# bbtc-logic.net
KiCad netlist of a schematic drawn in EAGLE
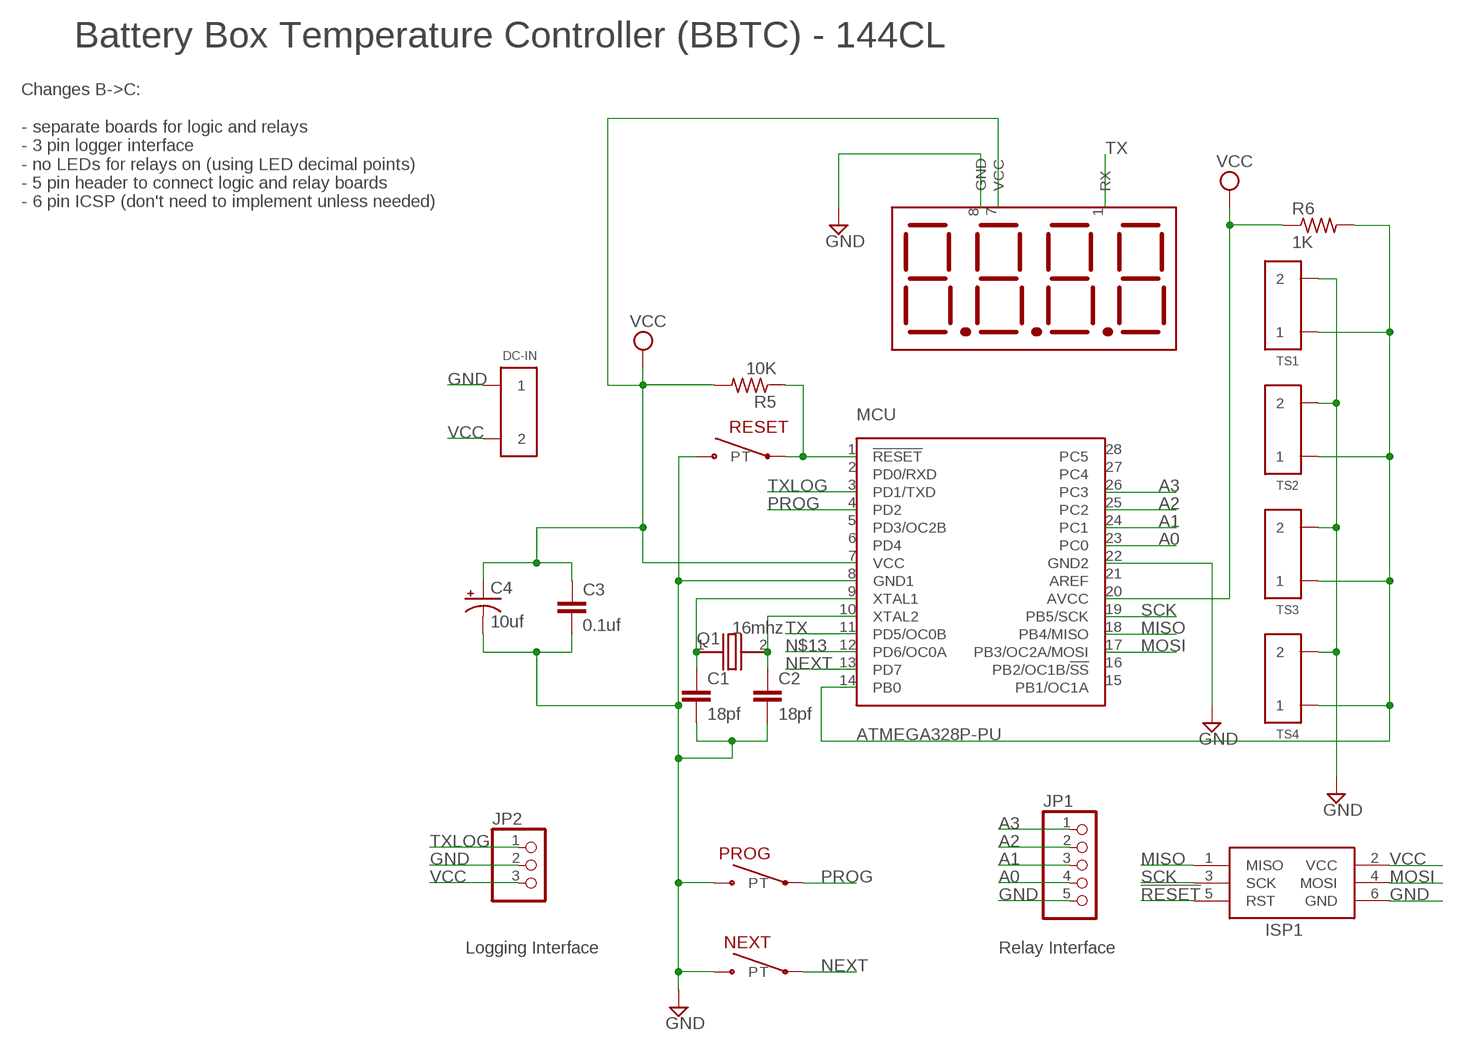
[diagram p0: schematic, sheet 1]

(export (version "E")
  (design (tool "Eeschema 10.0.6"))
  (components
    (comp (ref "4-DIG-DISPLAY")
      (value "4-DIGIT-DISPLAY")
      (footprint "eagle-import:3SIL-OF-8")
      (libsource (lib "eagle-import") (part "4-DIGIT-DISPLAY"))
    )
    (comp (ref "C1")
      (value "18pf")
      (footprint "eagle-import:C0805")
      (libsource (lib "eagle-import") (part "C-EUC0805"))
    )
    (comp (ref "C2")
      (value "18pf")
      (footprint "eagle-import:C0805")
      (libsource (lib "eagle-import") (part "C-EUC0805"))
    )
    (comp (ref "C3")
      (value "0.1uf")
      (footprint "eagle-import:C0805")
      (libsource (lib "eagle-import") (part "C-EUC0805"))
    )
    (comp (ref "C4")
      (value "10uf")
      (footprint "eagle-import:E2-4")
      (libsource (lib "eagle-import") (part "CPOL-USE2-4"))
    )
    (comp (ref "DC-IN")
      (value "SCREW-CLAMP-1255")
      (footprint "eagle-import:SCREW-CLAMP-ADAFRUIT-2X3.5MM")
      (libsource (lib "eagle-import") (part "SCREW-CLAMP-1255"))
    )
    (comp (ref "ISP1")
      (value "AVRISP-6")
      (footprint "eagle-import:AVRISP")
      (libsource (lib "eagle-import") (part "AVRISP-6"))
    )
    (comp (ref "JP1")
      (value "PINHD-1X5")
      (footprint "eagle-import:1X05")
      (libsource (lib "eagle-import") (part "PINHD-1X5"))
    )
    (comp (ref "JP2")
      (value "PINHD-1X3")
      (footprint "eagle-import:1X03")
      (libsource (lib "eagle-import") (part "PINHD-1X3"))
    )
    (comp (ref "MCU")
      (value "ATMEGA328P-PU")
      (footprint "eagle-import:DIL28-3")
      (libsource (lib "eagle-import") (part "ATMEGA328P-PU"))
    )
    (comp (ref "NEXT")
      (value "SWITCH-SPST-NEW")
      (footprint "eagle-import:SWITCH-ADAFRUIT-6MM-SLIM")
      (libsource (lib "eagle-import") (part "SWITCH-SPST-NEW"))
    )
    (comp (ref "PROG")
      (value "SWITCH-SPST-NEW")
      (footprint "eagle-import:SWITCH-ADAFRUIT-6MM-SLIM")
      (libsource (lib "eagle-import") (part "SWITCH-SPST-NEW"))
    )
    (comp (ref "Q1")
      (value "16mhz")
      (footprint "eagle-import:CRYSTAL-5X3.2MM-1024")
      (libsource (lib "eagle-import") (part "CRYSTAL-5X3.2MM1024"))
    )
    (comp (ref "R5")
      (value "10K")
      (footprint "eagle-import:R0805")
      (libsource (lib "eagle-import") (part "R-US_R0805"))
    )
    (comp (ref "R6")
      (value "1K")
      (footprint "eagle-import:M0805")
      (libsource (lib "eagle-import") (part "resistor_R-US_M0805"))
    )
    (comp (ref "RESET")
      (value "SWITCH-SPST-NEW")
      (footprint "eagle-import:SWITCH-ADAFRUIT-6MM-SLIM")
      (libsource (lib "eagle-import") (part "SWITCH-SPST-NEW"))
    )
    (comp (ref "TS1")
      (value "SCREW-CLAMP-1255")
      (footprint "eagle-import:SCREW-CLAMP-ADAFRUIT-2X3.5MM")
      (libsource (lib "eagle-import") (part "SCREW-CLAMP-1255"))
    )
    (comp (ref "TS2")
      (value "SCREW-CLAMP-1255")
      (footprint "eagle-import:SCREW-CLAMP-ADAFRUIT-2X3.5MM")
      (libsource (lib "eagle-import") (part "SCREW-CLAMP-1255"))
    )
    (comp (ref "TS3")
      (value "SCREW-CLAMP-1255")
      (footprint "eagle-import:SCREW-CLAMP-ADAFRUIT-2X3.5MM")
      (libsource (lib "eagle-import") (part "SCREW-CLAMP-1255"))
    )
    (comp (ref "TS4")
      (value "SCREW-CLAMP-1255")
      (footprint "eagle-import:SCREW-CLAMP-ADAFRUIT-2X3.5MM")
      (libsource (lib "eagle-import") (part "SCREW-CLAMP-1255"))
    )
  )
  (nets
    (net (code "1") (name "/A0") (class "Default")
      (node (ref "JP1") (pin "4") (pinfunction "4_4") (pintype "passive"))
      (node (ref "MCU") (pin "23") (pinfunction "PC0_23") (pintype "bidirectional"))
    )
    (net (code "2") (name "/A1") (class "Default")
      (node (ref "JP1") (pin "3") (pinfunction "3_3") (pintype "passive"))
      (node (ref "MCU") (pin "24") (pinfunction "PC1_24") (pintype "bidirectional"))
    )
    (net (code "3") (name "/A2") (class "Default")
      (node (ref "JP1") (pin "2") (pinfunction "2_2") (pintype "passive"))
      (node (ref "MCU") (pin "25") (pinfunction "PC2_25") (pintype "bidirectional"))
    )
    (net (code "4") (name "/A3") (class "Default")
      (node (ref "JP1") (pin "1") (pinfunction "1_1") (pintype "passive"))
      (node (ref "MCU") (pin "26") (pinfunction "PC3_26") (pintype "bidirectional"))
    )
    (net (code "5") (name "/MISO") (class "Default")
      (node (ref "ISP1") (pin "1") (pinfunction "MISO_1") (pintype "input"))
      (node (ref "MCU") (pin "18") (pinfunction "PB4/MISO_18") (pintype "bidirectional"))
    )
    (net (code "6") (name "/MOSI") (class "Default")
      (node (ref "ISP1") (pin "4") (pinfunction "MOSI_4") (pintype "output"))
      (node (ref "MCU") (pin "17") (pinfunction "PB3/OC2A/MOSI_17") (pintype "bidirectional"))
    )
    (net (code "7") (name "/N$13") (class "Default")
      (node (ref "MCU") (pin "12") (pinfunction "PD6/OC0A_12") (pintype "bidirectional"))
    )
    (net (code "8") (name "/NEXT") (class "Default")
      (node (ref "MCU") (pin "13") (pinfunction "PD7_13") (pintype "bidirectional"))
      (node (ref "NEXT") (pin "T") (pinfunction "T_T") (pintype "bidirectional"))
    )
    (net (code "9") (name "/PROG") (class "Default")
      (node (ref "MCU") (pin "4") (pinfunction "PD2_4") (pintype "bidirectional"))
      (node (ref "PROG") (pin "T") (pinfunction "T_T") (pintype "bidirectional"))
    )
    (net (code "10") (name "/SCK") (class "Default")
      (node (ref "ISP1") (pin "3") (pinfunction "SCK_3") (pintype "output"))
      (node (ref "MCU") (pin "19") (pinfunction "PB5/SCK_19") (pintype "bidirectional"))
    )
    (net (code "11") (name "/TX") (class "Default")
      (node (ref "4-DIG-DISPLAY") (pin "1") (pinfunction "RX_1") (pintype "bidirectional"))
      (node (ref "MCU") (pin "11") (pinfunction "PD5/OC0B_11") (pintype "bidirectional"))
    )
    (net (code "12") (name "/TXLOG") (class "Default")
      (node (ref "JP2") (pin "1") (pinfunction "1_1") (pintype "passive"))
      (node (ref "MCU") (pin "3") (pinfunction "PD1/TXD_3") (pintype "bidirectional"))
    )
    (net (code "13") (name "/~{RESET}") (class "Default")
      (node (ref "ISP1") (pin "5") (pinfunction "RST_5") (pintype "output"))
      (node (ref "MCU") (pin "1") (pinfunction "~{RESET}_1") (pintype "bidirectional"))
      (node (ref "R5") (pin "1") (pinfunction "1_1") (pintype "passive"))
      (node (ref "RESET") (pin "T") (pinfunction "T_T") (pintype "bidirectional"))
    )
    (net (code "14") (name "GND") (class "Default")
      (node (ref "4-DIG-DISPLAY") (pin "8") (pinfunction "GND_8") (pintype "bidirectional"))
      (node (ref "C1") (pin "2") (pinfunction "2_2") (pintype "passive"))
      (node (ref "C2") (pin "2") (pinfunction "2_2") (pintype "passive"))
      (node (ref "C3") (pin "2") (pinfunction "2_2") (pintype "passive"))
      (node (ref "C4") (pin "-") (pinfunction "-_-") (pintype "passive"))
      (node (ref "DC-IN") (pin "1") (pinfunction "1_1") (pintype "bidirectional"))
      (node (ref "ISP1") (pin "6") (pinfunction "GND_6") (pintype "power_in"))
      (node (ref "JP1") (pin "5") (pinfunction "5_5") (pintype "passive"))
      (node (ref "JP2") (pin "2") (pinfunction "2_2") (pintype "passive"))
      (node (ref "MCU") (pin "22") (pinfunction "GND2_22") (pintype "bidirectional"))
      (node (ref "MCU") (pin "8") (pinfunction "GND1_8") (pintype "bidirectional"))
      (node (ref "NEXT") (pin "P") (pinfunction "P_P") (pintype "bidirectional"))
      (node (ref "PROG") (pin "P") (pinfunction "P_P") (pintype "bidirectional"))
      (node (ref "RESET") (pin "P") (pinfunction "P_P") (pintype "bidirectional"))
      (node (ref "TS1") (pin "2") (pinfunction "2_2") (pintype "bidirectional"))
      (node (ref "TS2") (pin "2") (pinfunction "2_2") (pintype "bidirectional"))
      (node (ref "TS3") (pin "2") (pinfunction "2_2") (pintype "bidirectional"))
      (node (ref "TS4") (pin "2") (pinfunction "2_2") (pintype "bidirectional"))
    )
    (net (code "15") (name "Net-(MCU-PB0)") (class "Default")
      (node (ref "MCU") (pin "14") (pinfunction "PB0_14") (pintype "bidirectional"))
      (node (ref "R6") (pin "2") (pinfunction "2_2") (pintype "passive"))
      (node (ref "TS1") (pin "1") (pinfunction "1_1") (pintype "bidirectional"))
      (node (ref "TS2") (pin "1") (pinfunction "1_1") (pintype "bidirectional"))
      (node (ref "TS3") (pin "1") (pinfunction "1_1") (pintype "bidirectional"))
      (node (ref "TS4") (pin "1") (pinfunction "1_1") (pintype "bidirectional"))
    )
    (net (code "16") (name "Net-(MCU-XTAL1)") (class "Default")
      (node (ref "C1") (pin "1") (pinfunction "1_1") (pintype "passive"))
      (node (ref "MCU") (pin "9") (pinfunction "XTAL1_9") (pintype "bidirectional"))
      (node (ref "Q1") (pin "1") (pinfunction "1_1") (pintype "bidirectional"))
    )
    (net (code "17") (name "Net-(MCU-XTAL2)") (class "Default")
      (node (ref "C2") (pin "1") (pinfunction "1_1") (pintype "passive"))
      (node (ref "MCU") (pin "10") (pinfunction "XTAL2_10") (pintype "bidirectional"))
      (node (ref "Q1") (pin "2") (pinfunction "2_2") (pintype "bidirectional"))
    )
    (net (code "18") (name "VCC") (class "Default")
      (node (ref "4-DIG-DISPLAY") (pin "7") (pinfunction "VCC_7") (pintype "bidirectional"))
      (node (ref "C3") (pin "1") (pinfunction "1_1") (pintype "passive"))
      (node (ref "C4") (pin "+") (pinfunction "+_+") (pintype "passive"))
      (node (ref "DC-IN") (pin "2") (pinfunction "2_2") (pintype "bidirectional"))
      (node (ref "ISP1") (pin "2") (pinfunction "VCC_2") (pintype "power_in"))
      (node (ref "JP2") (pin "3") (pinfunction "3_3") (pintype "passive"))
      (node (ref "MCU") (pin "20") (pinfunction "AVCC_20") (pintype "bidirectional"))
      (node (ref "MCU") (pin "7") (pinfunction "VCC_7") (pintype "bidirectional"))
      (node (ref "R5") (pin "2") (pinfunction "2_2") (pintype "passive"))
      (node (ref "R6") (pin "1") (pinfunction "1_1") (pintype "passive"))
    )
    (net (code "19") (name "unconnected-(MCU-AREF-Pad21)") (class "Default")
      (node (ref "MCU") (pin "21") (pinfunction "AREF_21") (pintype "bidirectional"))
    )
    (net (code "20") (name "unconnected-(MCU-PB1{slash}OC1A-Pad15)") (class "Default")
      (node (ref "MCU") (pin "15") (pinfunction "PB1/OC1A_15") (pintype "bidirectional"))
    )
    (net (code "21") (name "unconnected-(MCU-PB2{slash}OC1B{slash}~{SS}-Pad16)") (class "Default")
      (node (ref "MCU") (pin "16") (pinfunction "PB2/OC1B/~{SS}_16") (pintype "bidirectional"))
    )
    (net (code "22") (name "unconnected-(MCU-PC4-Pad27)") (class "Default")
      (node (ref "MCU") (pin "27") (pinfunction "PC4_27") (pintype "bidirectional"))
    )
    (net (code "23") (name "unconnected-(MCU-PC5-Pad28)") (class "Default")
      (node (ref "MCU") (pin "28") (pinfunction "PC5_28") (pintype "bidirectional"))
    )
    (net (code "24") (name "unconnected-(MCU-PD0{slash}RXD-Pad2)") (class "Default")
      (node (ref "MCU") (pin "2") (pinfunction "PD0/RXD_2") (pintype "bidirectional"))
    )
    (net (code "25") (name "unconnected-(MCU-PD3{slash}OC2B-Pad5)") (class "Default")
      (node (ref "MCU") (pin "5") (pinfunction "PD3/OC2B_5") (pintype "bidirectional"))
    )
    (net (code "26") (name "unconnected-(MCU-PD4-Pad6)") (class "Default")
      (node (ref "MCU") (pin "6") (pinfunction "PD4_6") (pintype "bidirectional"))
    )
  )
)
